# Sensor.net
KiCad netlist of a schematic drawn in Altium Designer
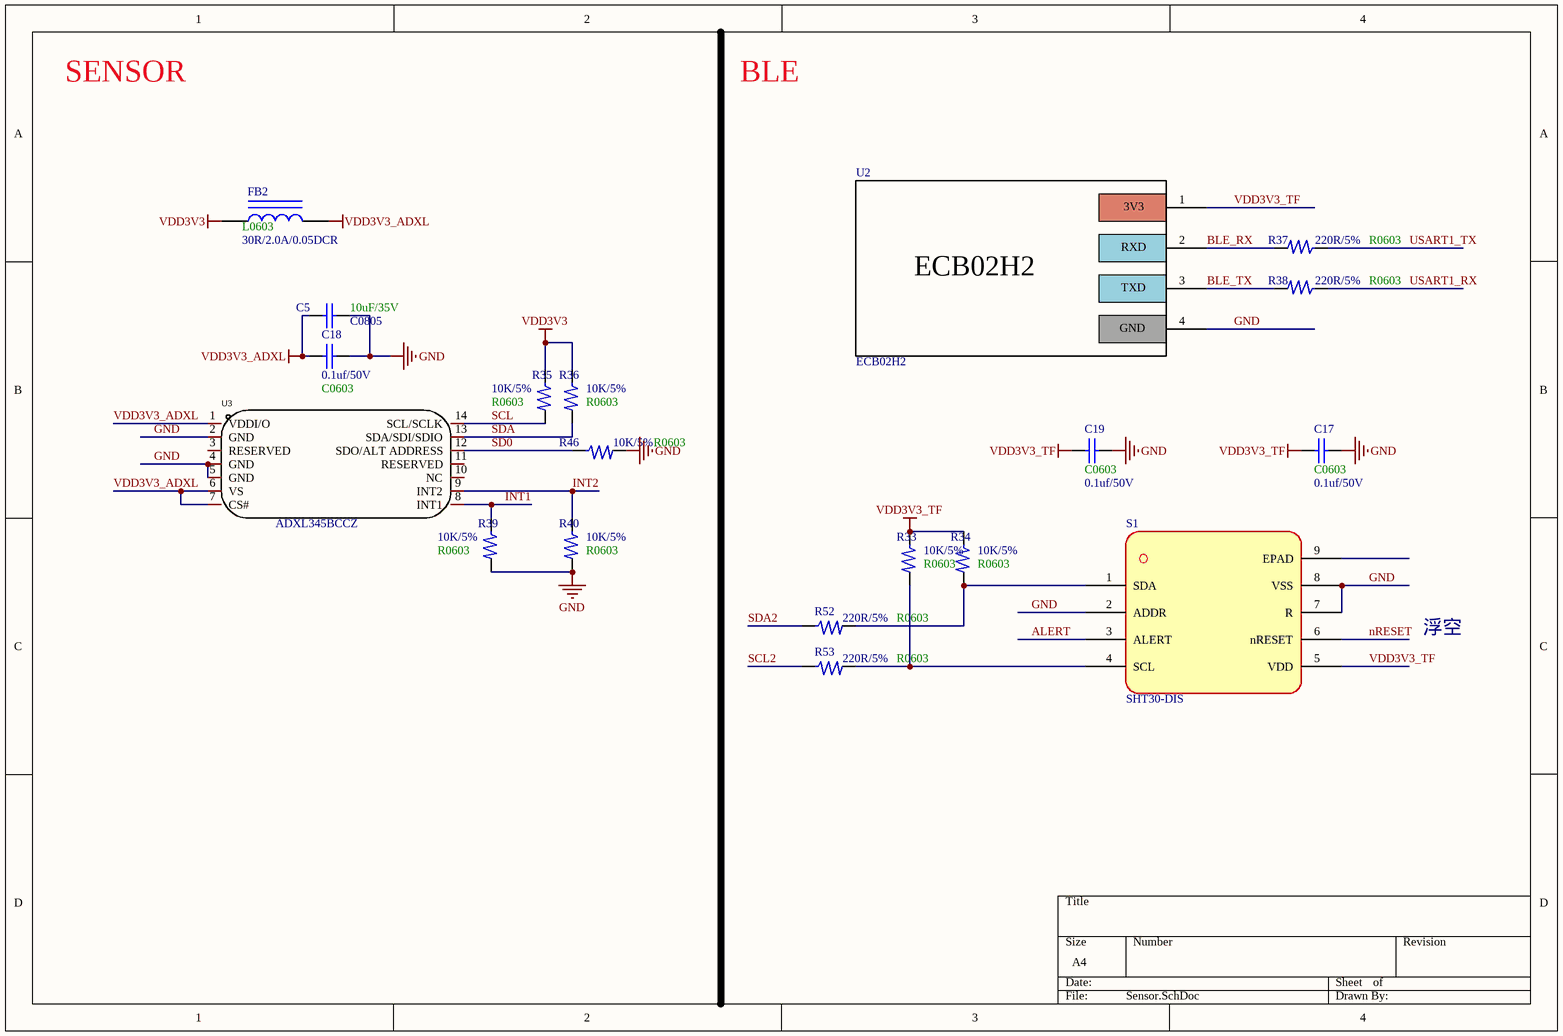
[diagram p0: Sensor.SchDoc]

(export (version "E")
  (design (tool "Eeschema 10.0.6"))
  (components
    (comp (ref "C5")
      (value "10uF/35V")
      (footprint "0805_C")
      (description "10uf/35V")
      (fields (field (name "ALTIUM_VALUE") "C0805"))
      (libsource (lib "*") (part "CAP"))
    )
    (comp (ref "C17")
      (value "C0603")
      (footprint "0603_C")
      (description "0.1uf/50V")
      (fields (field (name "ALTIUM_VALUE") "0.1uf/50V"))
      (libsource (lib "*") (part "CAP"))
    )
    (comp (ref "C18")
      (value "0.1uf/50V")
      (footprint "C0603")
      (description "Capacitor")
      (libsource (lib "*") (part "CAP"))
    )
    (comp (ref "C19")
      (value "C0603")
      (footprint "0603_C")
      (description "0.1uf/50V")
      (fields (field (name "ALTIUM_VALUE") "0.1uf/50V"))
      (libsource (lib "*") (part "CAP"))
    )
    (comp (ref "FB2")
      (value "30R/2.0A/0.05DCR")
      (footprint "0603_L")
      (description "贴片电感")
      (fields (field (name "PACKAGE") "L0603"))
      (libsource (lib "Miscellaneous Devices LC") (part "0603 3.9nH 0.3nH"))
    )
    (comp (ref "R33") (value "10K/5%") (footprint "R0603") (libsource (lib "*") (part "电阻")))
    (comp (ref "R34") (value "10K/5%") (footprint "R0603") (libsource (lib "*") (part "电阻")))
    (comp (ref "R35") (value "10K/5%") (footprint "R0603") (libsource (lib "*") (part "电阻")))
    (comp (ref "R36") (value "10K/5%") (footprint "R0603") (libsource (lib "*") (part "电阻")))
    (comp (ref "R37") (value "220R/5%") (footprint "R0603") (libsource (lib "*") (part "电阻")))
    (comp (ref "R38") (value "220R/5%") (footprint "R0603") (libsource (lib "*") (part "电阻")))
    (comp (ref "R39") (value "10K/5%") (footprint "R0603") (libsource (lib "*") (part "电阻")))
    (comp (ref "R40") (value "10K/5%") (footprint "R0603") (libsource (lib "*") (part "电阻")))
    (comp (ref "R46") (value "10K/5%") (footprint "R0603") (libsource (lib "*") (part "电阻")))
    (comp (ref "R52") (value "220R/5%") (footprint "R0603") (libsource (lib "*") (part "电阻")))
    (comp (ref "R53") (value "220R/5%") (footprint "R0603") (libsource (lib "*") (part "电阻")))
    (comp (ref "S1") (value "SHT30-DIS") (footprint "DFN-8") (libsource (lib "*") (part "SHT30-DIS-B")))
    (comp (ref "U2")
      (value "ECB02H2")
      (footprint "HDR1X4")
      (libsource (lib "ECB02蓝牙模块原理图库") (part "ECB02H2"))
    )
    (comp (ref "U3")
      (value "ADXL345BCCZ")
      (footprint "LGA-14_L5.0-W3.0-P0.80-BL")
      (fields (field (name "MANUFACTURER") "ADI(亚德诺)/LINEAR"))
      (libsource (lib "altium-import") (part "root_0_ADXL345BCCZ_"))
    )
  )
  (nets
    (net (code "1") (name "/ALERT") (class "Default")
      (node (ref "S1") (pin "3") (pinfunction "ALERT_3") (pintype "passive"))
    )
    (net (code "2") (name "/BLE_RX") (class "Default")
      (node (ref "R37") (pin "1") (pintype "passive"))
      (node (ref "U2") (pin "2") (pinfunction "2_2") (pintype "passive"))
    )
    (net (code "3") (name "/BLE_TX") (class "Default")
      (node (ref "R38") (pin "1") (pintype "passive"))
      (node (ref "U2") (pin "3") (pinfunction "3_3") (pintype "passive"))
    )
    (net (code "4") (name "/INT1") (class "Default")
      (node (ref "R39") (pin "2") (pintype "passive"))
      (node (ref "U3") (pin "8") (pinfunction "INT1_8") (pintype "passive"))
    )
    (net (code "5") (name "/INT2") (class "Default")
      (node (ref "R40") (pin "2") (pintype "passive"))
      (node (ref "U3") (pin "9") (pinfunction "INT2_9") (pintype "passive"))
    )
    (net (code "6") (name "/SCL") (class "Default")
      (node (ref "R35") (pin "1") (pintype "passive"))
      (node (ref "U3") (pin "14") (pinfunction "SCL/SCLK_14") (pintype "passive"))
    )
    (net (code "7") (name "/SCL2") (class "Default") (node (ref "R53") (pin "2") (pintype "passive")))
    (net (code "8") (name "/SD0") (class "Default")
      (node (ref "R46") (pin "2") (pintype "passive"))
      (node (ref "U3") (pin "12") (pinfunction "SDO/ALT_ADDRESS_12") (pintype "passive"))
    )
    (net (code "9") (name "/SDA") (class "Default")
      (node (ref "R36") (pin "1") (pintype "passive"))
      (node (ref "U3") (pin "13") (pinfunction "SDA/SDI/SDIO_13") (pintype "passive"))
    )
    (net (code "10") (name "/SDA2") (class "Default") (node (ref "R52") (pin "2") (pintype "passive")))
    (net (code "11") (name "/USART1_RX") (class "Default") (node (ref "R38") (pin "2") (pintype "passive")))
    (net (code "12") (name "/USART1_TX") (class "Default") (node (ref "R37") (pin "2") (pintype "passive")))
    (net (code "13") (name "/nRESET") (class "Default")
      (node (ref "S1") (pin "6") (pinfunction "nRESET_6") (pintype "passive"))
    )
    (net (code "14") (name "GND") (class "Default")
      (node (ref "C17") (pin "1") (pinfunction "1_1") (pintype "passive"))
      (node (ref "C18") (pin "2") (pinfunction "2_2") (pintype "passive"))
      (node (ref "C19") (pin "1") (pinfunction "1_1") (pintype "passive"))
      (node (ref "C5") (pin "2") (pinfunction "2_2") (pintype "passive"))
      (node (ref "R39") (pin "1") (pintype "passive"))
      (node (ref "R40") (pin "1") (pintype "passive"))
      (node (ref "R46") (pin "1") (pintype "passive"))
      (node (ref "S1") (pin "2") (pinfunction "ADDR_2") (pintype "passive"))
      (node (ref "S1") (pin "7") (pinfunction "R_7") (pintype "passive"))
      (node (ref "S1") (pin "8") (pinfunction "VSS_8") (pintype "passive"))
      (node (ref "U2") (pin "4") (pinfunction "4_4") (pintype "passive"))
      (node (ref "U3") (pin "2") (pinfunction "GND_2") (pintype "passive"))
      (node (ref "U3") (pin "4") (pinfunction "GND_4") (pintype "passive"))
      (node (ref "U3") (pin "5") (pinfunction "GND_5") (pintype "passive"))
    )
    (net (code "15") (name "Net-(S1-SCL)") (class "Default")
      (node (ref "R33") (pin "1") (pintype "passive"))
      (node (ref "R53") (pin "1") (pintype "passive"))
      (node (ref "S1") (pin "4") (pinfunction "SCL_4") (pintype "passive"))
    )
    (net (code "16") (name "Net-(S1-SDA)") (class "Default")
      (node (ref "R34") (pin "1") (pintype "passive"))
      (node (ref "R52") (pin "1") (pintype "passive"))
      (node (ref "S1") (pin "1") (pinfunction "SDA_1") (pintype "passive"))
    )
    (net (code "17") (name "VDD3V3") (class "Default")
      (node (ref "FB2") (pin "1") (pinfunction "1_1") (pintype "passive"))
      (node (ref "R35") (pin "2") (pintype "passive"))
      (node (ref "R36") (pin "2") (pintype "passive"))
    )
    (net (code "18") (name "VDD3V3_ADXL") (class "Default")
      (node (ref "C18") (pin "1") (pinfunction "1_1") (pintype "passive"))
      (node (ref "C5") (pin "1") (pinfunction "1_1") (pintype "passive"))
      (node (ref "FB2") (pin "2") (pinfunction "2_2") (pintype "passive"))
      (node (ref "U3") (pin "1") (pinfunction "VDDI/O_1") (pintype "passive"))
      (node (ref "U3") (pin "6") (pinfunction "VS_6") (pintype "passive"))
      (node (ref "U3") (pin "7") (pinfunction "CS#_7") (pintype "passive"))
    )
    (net (code "19") (name "VDD3V3_TF") (class "Default")
      (node (ref "C17") (pin "2") (pinfunction "2_2") (pintype "passive"))
      (node (ref "C19") (pin "2") (pinfunction "2_2") (pintype "passive"))
      (node (ref "R33") (pin "2") (pintype "passive"))
      (node (ref "R34") (pin "2") (pintype "passive"))
      (node (ref "S1") (pin "5") (pinfunction "VDD_5") (pintype "passive"))
      (node (ref "U2") (pin "1") (pinfunction "1_1") (pintype "passive"))
    )
    (net (code "20") (name "unconnected-(S1-EPAD-Pad9)") (class "Default")
      (node (ref "S1") (pin "9") (pinfunction "EPAD_9") (pintype "passive"))
    )
    (net (code "21") (name "unconnected-(U3-NC-Pad10)") (class "Default")
      (node (ref "U3") (pin "10") (pinfunction "NC_10") (pintype "passive"))
    )
    (net (code "22") (name "unconnected-(U3-RESERVED-Pad3)") (class "Default")
      (node (ref "U3") (pin "3") (pinfunction "RESERVED_3") (pintype "passive"))
    )
    (net (code "23") (name "unconnected-(U3-RESERVED-Pad11)") (class "Default")
      (node (ref "U3") (pin "11") (pinfunction "RESERVED_11") (pintype "passive"))
    )
  )
)
